# CH340C9R-R1.net
KiCad netlist of a schematic drawn in Altium Designer
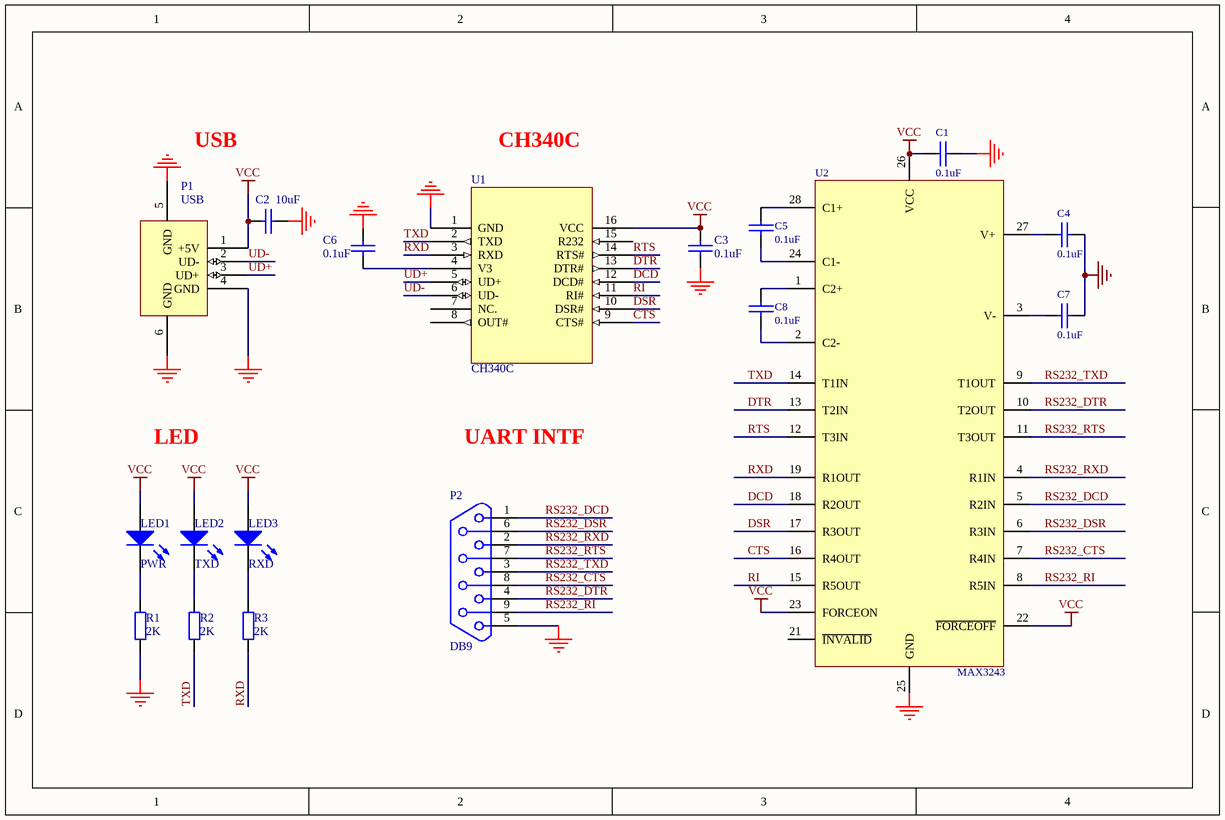
[diagram p0: CH340C9R-R1.SchDoc]

(export (version "E")
  (design (tool "Eeschema 10.0.6"))
  (components
    (comp (ref "C1") (value "0.1uF") (footprint "0603_C") (libsource (lib "*") (part "CAP")))
    (comp (ref "C2")
      (value "10uF")
      (footprint "3216_C")
      (description "Capacitor")
      (libsource (lib "") (part "CAP_1"))
    )
    (comp (ref "C3")
      (value "0.1uF")
      (footprint "0603_C")
      (description "Capacitor")
      (libsource (lib "") (part "CAP_1"))
    )
    (comp (ref "C4") (value "0.1uF") (footprint "0603_C") (libsource (lib "*") (part "CAP")))
    (comp (ref "C5") (value "0.1uF") (footprint "0603_C") (libsource (lib "*") (part "CAP")))
    (comp (ref "C6")
      (value "0.1uF")
      (footprint "0603_C")
      (description "Capacitor")
      (libsource (lib "") (part "CAP_1"))
    )
    (comp (ref "C7") (value "0.1uF") (footprint "0603_C") (libsource (lib "*") (part "CAP")))
    (comp (ref "C8") (value "0.1uF") (footprint "0603_C") (libsource (lib "*") (part "CAP")))
    (comp (ref "LED1")
      (value "PWR")
      (footprint "0603+")
      (description "Typical RED, GREEN, YELLOW, AMBER GaAs LED")
      (libsource (lib "*") (part "LED2"))
    )
    (comp (ref "LED2")
      (value "TXD")
      (footprint "0603+")
      (description "Typical RED, GREEN, YELLOW, AMBER GaAs LED")
      (libsource (lib "*") (part "LED2"))
    )
    (comp (ref "LED3")
      (value "RXD")
      (footprint "0603+")
      (description "Typical RED, GREEN, YELLOW, AMBER GaAs LED")
      (libsource (lib "*") (part "LED2"))
    )
    (comp (ref "P1") (value "USB") (footprint "USBAM") (libsource (lib "*") (part "USB")))
    (comp (ref "P2") (value "DB9") (footprint "DB9-PAD-M") (libsource (lib "*") (part "DB9")))
    (comp (ref "R1")
      (value "2K")
      (footprint "0603")
      (description "Resistor")
      (libsource (lib "*") (part "Res2"))
    )
    (comp (ref "R2")
      (value "2K")
      (footprint "0603")
      (description "Resistor")
      (libsource (lib "*") (part "Res2"))
    )
    (comp (ref "R3")
      (value "2K")
      (footprint "0603")
      (description "Resistor")
      (libsource (lib "*") (part "Res2"))
    )
    (comp (ref "U1")
      (value "CH340C")
      (footprint "SOP16")
      (description "USB to TTL Serial / UART")
      (libsource (lib "CHXXXSCH") (part "CH340C"))
    )
    (comp (ref "U2") (value "MAX3243") (footprint "SSOP28") (libsource (lib "*") (part "MAX3243")))
  )
  (nets
    (net (code "1") (name "/CTS") (class "Default")
      (node (ref "U1") (pin "9") (pinfunction "CTS#_9") (pintype "input"))
      (node (ref "U2") (pin "16") (pinfunction "R4OUT_16") (pintype "passive"))
    )
    (net (code "2") (name "/DCD") (class "Default")
      (node (ref "U1") (pin "12") (pinfunction "DCD#_12") (pintype "input"))
      (node (ref "U2") (pin "18") (pinfunction "R2OUT_18") (pintype "passive"))
    )
    (net (code "3") (name "/DSR") (class "Default")
      (node (ref "U1") (pin "10") (pinfunction "DSR#_10") (pintype "input"))
      (node (ref "U2") (pin "17") (pinfunction "R3OUT_17") (pintype "passive"))
    )
    (net (code "4") (name "/DTR") (class "Default")
      (node (ref "U1") (pin "13") (pinfunction "DTR#_13") (pintype "output"))
      (node (ref "U2") (pin "13") (pinfunction "T2IN_13") (pintype "passive"))
    )
    (net (code "5") (name "/RI") (class "Default")
      (node (ref "U1") (pin "11") (pinfunction "RI#_11") (pintype "input"))
      (node (ref "U2") (pin "15") (pinfunction "R5OUT_15") (pintype "passive"))
    )
    (net (code "6") (name "/RS232_CTS") (class "Default")
      (node (ref "P2") (pin "8") (pinfunction "8_8") (pintype "passive"))
      (node (ref "U2") (pin "7") (pinfunction "R4IN_7") (pintype "passive"))
    )
    (net (code "7") (name "/RS232_DCD") (class "Default")
      (node (ref "P2") (pin "1") (pinfunction "1_1") (pintype "passive"))
      (node (ref "U2") (pin "5") (pinfunction "R2IN_5") (pintype "passive"))
    )
    (net (code "8") (name "/RS232_DSR") (class "Default")
      (node (ref "P2") (pin "6") (pinfunction "6_6") (pintype "passive"))
      (node (ref "U2") (pin "6") (pinfunction "R3IN_6") (pintype "passive"))
    )
    (net (code "9") (name "/RS232_DTR") (class "Default")
      (node (ref "P2") (pin "4") (pinfunction "4_4") (pintype "passive"))
      (node (ref "U2") (pin "10") (pinfunction "T2OUT_10") (pintype "passive"))
    )
    (net (code "10") (name "/RS232_RI") (class "Default")
      (node (ref "P2") (pin "9") (pinfunction "9_9") (pintype "passive"))
      (node (ref "U2") (pin "8") (pinfunction "R5IN_8") (pintype "passive"))
    )
    (net (code "11") (name "/RS232_RTS") (class "Default")
      (node (ref "P2") (pin "7") (pinfunction "7_7") (pintype "passive"))
      (node (ref "U2") (pin "11") (pinfunction "T3OUT_11") (pintype "passive"))
    )
    (net (code "12") (name "/RS232_RXD") (class "Default")
      (node (ref "P2") (pin "2") (pinfunction "2_2") (pintype "passive"))
      (node (ref "U2") (pin "4") (pinfunction "R1IN_4") (pintype "passive"))
    )
    (net (code "13") (name "/RS232_TXD") (class "Default")
      (node (ref "P2") (pin "3") (pinfunction "3_3") (pintype "passive"))
      (node (ref "U2") (pin "9") (pinfunction "T1OUT_9") (pintype "passive"))
    )
    (net (code "14") (name "/RTS") (class "Default")
      (node (ref "U1") (pin "14") (pinfunction "RTS#_14") (pintype "output"))
      (node (ref "U2") (pin "12") (pinfunction "T3IN_12") (pintype "passive"))
    )
    (net (code "15") (name "/RXD") (class "Default")
      (node (ref "R3") (pin "2") (pinfunction "2_2") (pintype "passive"))
      (node (ref "U1") (pin "3") (pinfunction "RXD_3") (pintype "input"))
      (node (ref "U2") (pin "19") (pinfunction "R1OUT_19") (pintype "passive"))
    )
    (net (code "16") (name "/TXD") (class "Default")
      (node (ref "R2") (pin "2") (pinfunction "2_2") (pintype "passive"))
      (node (ref "U1") (pin "2") (pinfunction "TXD_2") (pintype "output"))
      (node (ref "U2") (pin "14") (pinfunction "T1IN_14") (pintype "passive"))
    )
    (net (code "17") (name "/UD+") (class "Default")
      (node (ref "P1") (pin "3") (pinfunction "UD+_3") (pintype "bidirectional"))
      (node (ref "U1") (pin "5") (pinfunction "UD+_5") (pintype "bidirectional"))
    )
    (net (code "18") (name "/UD-") (class "Default")
      (node (ref "P1") (pin "2") (pinfunction "UD-_2") (pintype "bidirectional"))
      (node (ref "U1") (pin "6") (pinfunction "UD-_6") (pintype "bidirectional"))
    )
    (net (code "19") (name "GND") (class "Default")
      (node (ref "C1") (pin "2") (pintype "passive"))
      (node (ref "C2") (pin "2") (pinfunction "2_2") (pintype "passive"))
      (node (ref "C3") (pin "2") (pinfunction "2_2") (pintype "passive"))
      (node (ref "C4") (pin "2") (pintype "passive"))
      (node (ref "C6") (pin "2") (pinfunction "2_2") (pintype "passive"))
      (node (ref "C7") (pin "2") (pintype "passive"))
      (node (ref "P1") (pin "4") (pinfunction "GND_4") (pintype "power_in"))
      (node (ref "P1") (pin "5") (pinfunction "GND_5") (pintype "power_in"))
      (node (ref "P1") (pin "6") (pinfunction "GND_6") (pintype "power_in"))
      (node (ref "P2") (pin "5") (pinfunction "5_5") (pintype "passive"))
      (node (ref "R1") (pin "2") (pinfunction "2_2") (pintype "passive"))
      (node (ref "U1") (pin "1") (pinfunction "GND_1") (pintype "power_in"))
      (node (ref "U2") (pin "25") (pinfunction "GND_25") (pintype "passive"))
    )
    (net (code "20") (name "Net-(LED1-K)") (class "Default")
      (node (ref "LED1") (pin "2") (pinfunction "K_2") (pintype "passive"))
      (node (ref "R1") (pin "1") (pinfunction "1_1") (pintype "passive"))
    )
    (net (code "21") (name "Net-(LED2-K)") (class "Default")
      (node (ref "LED2") (pin "2") (pinfunction "K_2") (pintype "passive"))
      (node (ref "R2") (pin "1") (pinfunction "1_1") (pintype "passive"))
    )
    (net (code "22") (name "Net-(LED3-K)") (class "Default")
      (node (ref "LED3") (pin "2") (pinfunction "K_2") (pintype "passive"))
      (node (ref "R3") (pin "1") (pinfunction "1_1") (pintype "passive"))
    )
    (net (code "23") (name "Net-(U1-V3)") (class "Default")
      (node (ref "C6") (pin "1") (pinfunction "1_1") (pintype "passive"))
      (node (ref "U1") (pin "4") (pinfunction "V3_4") (pintype "power_in"))
    )
    (net (code "24") (name "Net-(U2-C1+)") (class "Default")
      (node (ref "C5") (pin "1") (pintype "passive"))
      (node (ref "U2") (pin "28") (pinfunction "C1+_28") (pintype "passive"))
    )
    (net (code "25") (name "Net-(U2-C1-)") (class "Default")
      (node (ref "C5") (pin "2") (pintype "passive"))
      (node (ref "U2") (pin "24") (pinfunction "C1-_24") (pintype "passive"))
    )
    (net (code "26") (name "Net-(U2-C2+)") (class "Default")
      (node (ref "C8") (pin "1") (pintype "passive"))
      (node (ref "U2") (pin "1") (pinfunction "C2+_1") (pintype "passive"))
    )
    (net (code "27") (name "Net-(U2-C2-)") (class "Default")
      (node (ref "C8") (pin "2") (pintype "passive"))
      (node (ref "U2") (pin "2") (pinfunction "C2-_2") (pintype "passive"))
    )
    (net (code "28") (name "Net-(U2-V+)") (class "Default")
      (node (ref "C4") (pin "1") (pintype "passive"))
      (node (ref "U2") (pin "27") (pinfunction "V+_27") (pintype "passive"))
    )
    (net (code "29") (name "Net-(U2-V-)") (class "Default")
      (node (ref "C7") (pin "1") (pintype "passive"))
      (node (ref "U2") (pin "3") (pinfunction "V-_3") (pintype "passive"))
    )
    (net (code "30") (name "VCC") (class "Default")
      (node (ref "C1") (pin "1") (pintype "passive"))
      (node (ref "C2") (pin "1") (pinfunction "1_1") (pintype "passive"))
      (node (ref "C3") (pin "1") (pinfunction "1_1") (pintype "passive"))
      (node (ref "LED1") (pin "1") (pinfunction "A_1") (pintype "passive"))
      (node (ref "LED2") (pin "1") (pinfunction "A_1") (pintype "passive"))
      (node (ref "LED3") (pin "1") (pinfunction "A_1") (pintype "passive"))
      (node (ref "P1") (pin "1") (pinfunction "+5V_1") (pintype "power_in"))
      (node (ref "U1") (pin "16") (pinfunction "VCC_16") (pintype "power_in"))
      (node (ref "U2") (pin "22") (pinfunction "~{FORCEOFF}_22") (pintype "passive"))
      (node (ref "U2") (pin "23") (pinfunction "FORCEON_23") (pintype "passive"))
      (node (ref "U2") (pin "26") (pinfunction "VCC_26") (pintype "passive"))
    )
    (net (code "31") (name "unconnected-(U1-NC.-Pad7)") (class "Default")
      (node (ref "U1") (pin "7") (pinfunction "NC._7") (pintype "passive"))
    )
    (net (code "32") (name "unconnected-(U1-OUT#-Pad8)") (class "Default")
      (node (ref "U1") (pin "8") (pinfunction "OUT#_8") (pintype "output"))
    )
    (net (code "33") (name "unconnected-(U1-R232-Pad15)") (class "Default")
      (node (ref "U1") (pin "15") (pinfunction "R232_15") (pintype "input"))
    )
    (net (code "34") (name "unconnected-(U2-~{INVALID}-Pad21)") (class "Default")
      (node (ref "U2") (pin "21") (pinfunction "~{INVALID}_21") (pintype "passive"))
    )
  )
)
